# LF_ADC.net
KiCad netlist of a schematic drawn in Altium Designer
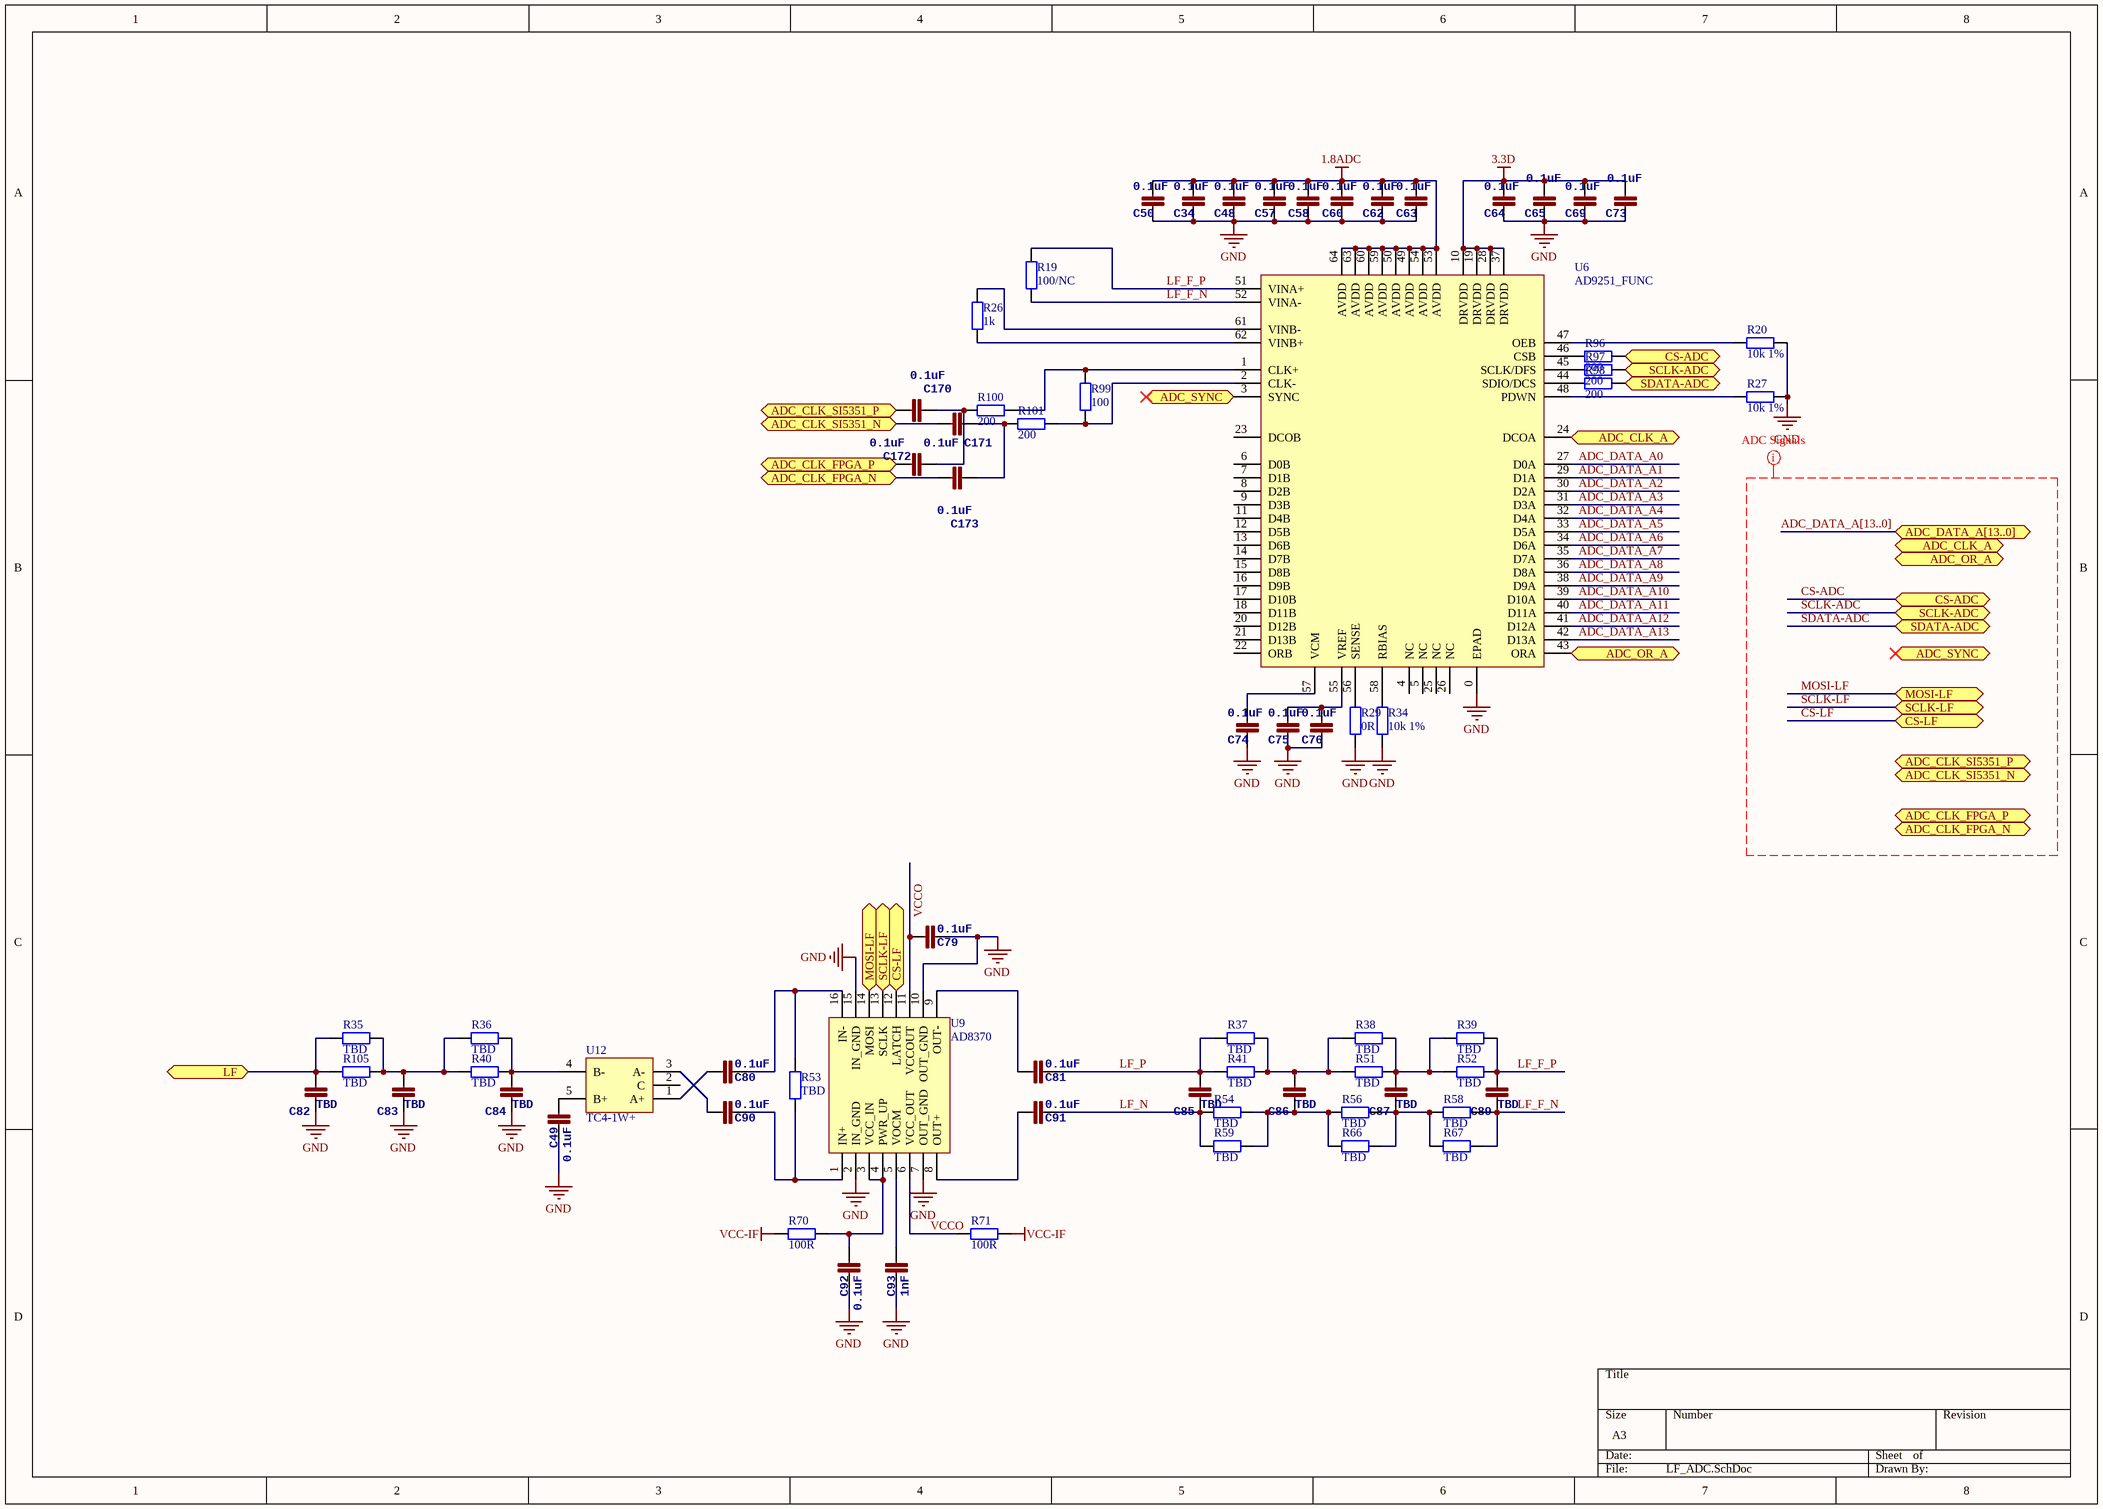
[diagram p0: LF_ADC.SchDoc]

(export (version "E")
  (design (tool "Eeschema 10.0.6"))
  (components
    (comp (ref "C34")
      (value "0.1uF")
      (footprint "0402")
      (description "<b>Capacitor</b>\nStandard 0603 ceramic capacitor, and 0.1\" leaded capacitor.")
      (fields (field (name "PARTNO") "CC0402ZRY5V7BB104"))
      (libsource (lib "*") (part "CAP0402-CAP"))
    )
    (comp (ref "C48")
      (value "0.1uF")
      (footprint "0402")
      (description "<b>Capacitor</b>\nStandard 0603 ceramic capacitor, and 0.1\" leaded capacitor.")
      (fields (field (name "PARTNO") "CC0402ZRY5V7BB104"))
      (libsource (lib "*") (part "CAP0402-CAP"))
    )
    (comp (ref "C49")
      (value "0.1uF")
      (footprint "0402")
      (description "<b>Capacitor</b>\nStandard 0603 ceramic capacitor, and 0.1\" leaded capacitor.")
      (fields (field (name "PARTNO") "CC0402ZRY5V7BB104"))
      (libsource (lib "*") (part "CAP0402-CAP"))
    )
    (comp (ref "C50")
      (value "0.1uF")
      (footprint "0402")
      (description "<b>Capacitor</b>\nStandard 0603 ceramic capacitor, and 0.1\" leaded capacitor.")
      (fields (field (name "PARTNO") "CC0402ZRY5V7BB104"))
      (libsource (lib "*") (part "CAP0402-CAP"))
    )
    (comp (ref "C57")
      (value "0.1uF")
      (footprint "0402")
      (description "<b>Capacitor</b>\nStandard 0603 ceramic capacitor, and 0.1\" leaded capacitor.")
      (fields (field (name "PARTNO") "CC0402ZRY5V7BB104"))
      (libsource (lib "*") (part "CAP0402-CAP"))
    )
    (comp (ref "C58")
      (value "0.1uF")
      (footprint "0402")
      (description "<b>Capacitor</b>\nStandard 0603 ceramic capacitor, and 0.1\" leaded capacitor.")
      (fields (field (name "PARTNO") "CC0402ZRY5V7BB104"))
      (libsource (lib "*") (part "CAP0402-CAP"))
    )
    (comp (ref "C60")
      (value "0.1uF")
      (footprint "0402")
      (description "<b>Capacitor</b>\nStandard 0603 ceramic capacitor, and 0.1\" leaded capacitor.")
      (fields (field (name "PARTNO") "CC0402ZRY5V7BB104"))
      (libsource (lib "*") (part "CAP0402-CAP"))
    )
    (comp (ref "C62")
      (value "0.1uF")
      (footprint "0402")
      (description "<b>Capacitor</b>\nStandard 0603 ceramic capacitor, and 0.1\" leaded capacitor.")
      (fields (field (name "PARTNO") "CC0402ZRY5V7BB104"))
      (libsource (lib "*") (part "CAP0402-CAP"))
    )
    (comp (ref "C63")
      (value "0.1uF")
      (footprint "0402")
      (description "<b>Capacitor</b>\nStandard 0603 ceramic capacitor, and 0.1\" leaded capacitor.")
      (fields (field (name "PARTNO") "CC0402ZRY5V7BB104"))
      (libsource (lib "*") (part "CAP0402-CAP"))
    )
    (comp (ref "C64")
      (value "0.1uF")
      (footprint "0402")
      (description "<b>Capacitor</b>\nStandard 0603 ceramic capacitor, and 0.1\" leaded capacitor.")
      (fields (field (name "PARTNO") "CC0402ZRY5V7BB104"))
      (libsource (lib "*") (part "CAP0402-CAP"))
    )
    (comp (ref "C65")
      (value "0.1uF")
      (footprint "0402")
      (description "<b>Capacitor</b>\nStandard 0603 ceramic capacitor, and 0.1\" leaded capacitor.")
      (fields (field (name "PARTNO") "CC0402ZRY5V7BB104"))
      (libsource (lib "*") (part "CAP0402-CAP"))
    )
    (comp (ref "C69")
      (value "0.1uF")
      (footprint "0402")
      (description "<b>Capacitor</b>\nStandard 0603 ceramic capacitor, and 0.1\" leaded capacitor.")
      (fields (field (name "PARTNO") "CC0402ZRY5V7BB104"))
      (libsource (lib "*") (part "CAP0402-CAP"))
    )
    (comp (ref "C73")
      (value "0.1uF")
      (footprint "0402")
      (description "<b>Capacitor</b>\nStandard 0603 ceramic capacitor, and 0.1\" leaded capacitor.")
      (fields (field (name "PARTNO") "CC0402ZRY5V7BB104"))
      (libsource (lib "*") (part "CAP0402-CAP"))
    )
    (comp (ref "C74")
      (value "0.1uF")
      (footprint "0402")
      (description "<b>Capacitor</b>\nStandard 0603 ceramic capacitor, and 0.1\" leaded capacitor.")
      (fields (field (name "PARTNO") "CC0402ZRY5V7BB104"))
      (libsource (lib "*") (part "CAP0402-CAP"))
    )
    (comp (ref "C75")
      (value "0.1uF")
      (footprint "0402")
      (description "<b>Capacitor</b>\nStandard 0603 ceramic capacitor, and 0.1\" leaded capacitor.")
      (fields (field (name "PARTNO") "CC0402ZRY5V7BB104"))
      (libsource (lib "*") (part "CAP0402-CAP"))
    )
    (comp (ref "C76")
      (value "0.1uF")
      (footprint "0402")
      (description "<b>Capacitor</b>\nStandard 0603 ceramic capacitor, and 0.1\" leaded capacitor.")
      (fields (field (name "PARTNO") "CC0402ZRY5V7BB104"))
      (libsource (lib "*") (part "CAP0402-CAP"))
    )
    (comp (ref "C79")
      (value "0.1uF")
      (footprint "0402")
      (description "<b>Capacitor</b>\nStandard 0603 ceramic capacitor, and 0.1\" leaded capacitor.")
      (fields (field (name "PARTNO") "CC0402ZRY5V7BB104"))
      (libsource (lib "") (part "CAP0402-CAP_1"))
    )
    (comp (ref "C80")
      (value "0.1uF")
      (footprint "0402")
      (description "<b>Capacitor</b>\nStandard 0603 ceramic capacitor, and 0.1\" leaded capacitor.")
      (fields (field (name "PARTNO") "CC0402ZRY5V7BB104"))
      (libsource (lib "") (part "CAP0402-CAP_1"))
    )
    (comp (ref "C81")
      (value "0.1uF")
      (footprint "0402")
      (description "<b>Capacitor</b>\nStandard 0603 ceramic capacitor, and 0.1\" leaded capacitor.")
      (fields (field (name "PARTNO") "CC0402ZRY5V7BB104"))
      (libsource (lib "") (part "CAP0402-CAP_1"))
    )
    (comp (ref "C82")
      (value "TBD")
      (footprint "0402")
      (description "<b>Capacitor</b>\nStandard 0603 ceramic capacitor, and 0.1\" leaded capacitor.")
      (fields (field (name "PARTNO") "CC0402ZRY5V7BB104"))
      (libsource (lib "") (part "CAP0402-CAP_2"))
    )
    (comp (ref "C83")
      (value "TBD")
      (footprint "0402")
      (description "<b>Capacitor</b>\nStandard 0603 ceramic capacitor, and 0.1\" leaded capacitor.")
      (fields (field (name "PARTNO") "CC0402ZRY5V7BB104"))
      (libsource (lib "") (part "CAP0402-CAP_2"))
    )
    (comp (ref "C84")
      (value "TBD")
      (footprint "0402")
      (description "<b>Capacitor</b>\nStandard 0603 ceramic capacitor, and 0.1\" leaded capacitor.")
      (fields (field (name "PARTNO") "CC0402ZRY5V7BB104"))
      (libsource (lib "") (part "CAP0402-CAP_2"))
    )
    (comp (ref "C85")
      (value "TBD")
      (footprint "0402")
      (description "<b>Capacitor</b>\nStandard 0603 ceramic capacitor, and 0.1\" leaded capacitor.")
      (fields (field (name "PARTNO") "CC0402ZRY5V7BB104"))
      (libsource (lib "") (part "CAP0402-CAP_2"))
    )
    (comp (ref "C86")
      (value "TBD")
      (footprint "0402")
      (description "<b>Capacitor</b>\nStandard 0603 ceramic capacitor, and 0.1\" leaded capacitor.")
      (fields (field (name "PARTNO") "CC0402ZRY5V7BB104"))
      (libsource (lib "") (part "CAP0402-CAP_2"))
    )
    (comp (ref "C87")
      (value "TBD")
      (footprint "0402")
      (description "<b>Capacitor</b>\nStandard 0603 ceramic capacitor, and 0.1\" leaded capacitor.")
      (fields (field (name "PARTNO") "CC0402ZRY5V7BB104"))
      (libsource (lib "") (part "CAP0402-CAP_2"))
    )
    (comp (ref "C89")
      (value "TBD")
      (footprint "0402")
      (description "<b>Capacitor</b>\nStandard 0603 ceramic capacitor, and 0.1\" leaded capacitor.")
      (fields (field (name "PARTNO") "CC0402ZRY5V7BB104"))
      (libsource (lib "") (part "CAP0402-CAP_2"))
    )
    (comp (ref "C90")
      (value "0.1uF")
      (footprint "0402")
      (description "<b>Capacitor</b>\nStandard 0603 ceramic capacitor, and 0.1\" leaded capacitor.")
      (fields (field (name "PARTNO") "CC0402ZRY5V7BB104"))
      (libsource (lib "") (part "CAP0402-CAP_1"))
    )
    (comp (ref "C91")
      (value "0.1uF")
      (footprint "0402")
      (description "<b>Capacitor</b>\nStandard 0603 ceramic capacitor, and 0.1\" leaded capacitor.")
      (fields (field (name "PARTNO") "CC0402ZRY5V7BB104"))
      (libsource (lib "") (part "CAP0402-CAP_1"))
    )
    (comp (ref "C92")
      (value "0.1uF")
      (footprint "0402")
      (description "<b>Capacitor</b>\nStandard 0603 ceramic capacitor, and 0.1\" leaded capacitor.")
      (fields (field (name "PARTNO") "CC0402ZRY5V7BB104"))
      (libsource (lib "*") (part "CAP0402-CAP"))
    )
    (comp (ref "C93")
      (value "1nF")
      (footprint "0402")
      (description "<b>Capacitor</b>\nStandard 0603 ceramic capacitor, and 0.1\" leaded capacitor.")
      (fields (field (name "PARTNO") "CC0402ZRY5V7BB104"))
      (libsource (lib "*") (part "CAP0402-CAP"))
    )
    (comp (ref "C170")
      (value "0.1uF")
      (footprint "0402")
      (description "<b>Capacitor</b>\nStandard 0603 ceramic capacitor, and 0.1\" leaded capacitor.")
      (fields (field (name "PARTNO") "CC0402ZRY5V7BB104"))
      (libsource (lib "") (part "CAP0402-CAP_1"))
    )
    (comp (ref "C171")
      (value "0.1uF")
      (footprint "0402")
      (description "<b>Capacitor</b>\nStandard 0603 ceramic capacitor, and 0.1\" leaded capacitor.")
      (fields (field (name "PARTNO") "CC0402ZRY5V7BB104"))
      (libsource (lib "") (part "CAP0402-CAP_1"))
    )
    (comp (ref "C172")
      (value "0.1uF")
      (footprint "0402")
      (description "<b>Capacitor</b>\nStandard 0603 ceramic capacitor, and 0.1\" leaded capacitor.")
      (fields (field (name "PARTNO") "CC0402ZRY5V7BB104"))
      (libsource (lib "") (part "CAP0402-CAP_1"))
    )
    (comp (ref "C173")
      (value "0.1uF")
      (footprint "0402")
      (description "<b>Capacitor</b>\nStandard 0603 ceramic capacitor, and 0.1\" leaded capacitor.")
      (fields (field (name "PARTNO") "CC0402ZRY5V7BB104"))
      (libsource (lib "") (part "CAP0402-CAP_1"))
    )
    (comp (ref "R19")
      (value "100/NC")
      (footprint "0402")
      (description "Resistor")
      (fields (field (name "PUBLISHER") "Altium Limited"))
      (libsource (lib "") (part "Res2_3"))
    )
    (comp (ref "R20")
      (value "10k 1%")
      (footprint "0402")
      (description "Resistor")
      (fields (field (name "PUBLISHER") "Altium Limited"))
      (libsource (lib "Miscellaneous Devices") (part "Res2"))
    )
    (comp (ref "R26")
      (value "1k")
      (footprint "0402")
      (description "Resistor")
      (fields (field (name "PUBLISHER") "Altium Limited"))
      (libsource (lib "") (part "Res2_3"))
    )
    (comp (ref "R27")
      (value "10k 1%")
      (footprint "0402")
      (description "Resistor")
      (fields (field (name "PUBLISHER") "Altium Limited"))
      (libsource (lib "Miscellaneous Devices") (part "Res2"))
    )
    (comp (ref "R29")
      (value "0R")
      (footprint "0402")
      (description "Resistor")
      (fields (field (name "PUBLISHER") "Altium Limited"))
      (libsource (lib "") (part "Res2_3"))
    )
    (comp (ref "R34")
      (value "10k 1%")
      (footprint "0402")
      (description "Resistor")
      (fields (field (name "PUBLISHER") "Altium Limited"))
      (libsource (lib "") (part "Res2_3"))
    )
    (comp (ref "R35")
      (value "TBD")
      (footprint "0402")
      (description "Resistor")
      (fields (field (name "PUBLISHER") "Altium Limited"))
      (libsource (lib "") (part "Res2_1"))
    )
    (comp (ref "R36")
      (value "TBD")
      (footprint "0402")
      (description "Resistor")
      (fields (field (name "PUBLISHER") "Altium Limited"))
      (libsource (lib "") (part "Res2_1"))
    )
    (comp (ref "R37")
      (value "TBD")
      (footprint "0402")
      (description "Resistor")
      (fields (field (name "PUBLISHER") "Altium Limited"))
      (libsource (lib "") (part "Res2_1"))
    )
    (comp (ref "R38")
      (value "TBD")
      (footprint "0402")
      (description "Resistor")
      (fields (field (name "PUBLISHER") "Altium Limited"))
      (libsource (lib "") (part "Res2_1"))
    )
    (comp (ref "R39")
      (value "TBD")
      (footprint "0402")
      (description "Resistor")
      (fields (field (name "PUBLISHER") "Altium Limited"))
      (libsource (lib "") (part "Res2_1"))
    )
    (comp (ref "R40")
      (value "TBD")
      (footprint "0402")
      (description "Resistor")
      (fields (field (name "PUBLISHER") "Altium Limited"))
      (libsource (lib "") (part "Res2_1"))
    )
    (comp (ref "R41")
      (value "TBD")
      (footprint "0402")
      (description "Resistor")
      (fields (field (name "PUBLISHER") "Altium Limited"))
      (libsource (lib "") (part "Res2_1"))
    )
    (comp (ref "R51")
      (value "TBD")
      (footprint "0402")
      (description "Resistor")
      (fields (field (name "PUBLISHER") "Altium Limited"))
      (libsource (lib "") (part "Res2_1"))
    )
    (comp (ref "R52")
      (value "TBD")
      (footprint "0402")
      (description "Resistor")
      (fields (field (name "PUBLISHER") "Altium Limited"))
      (libsource (lib "") (part "Res2_1"))
    )
    (comp (ref "R53")
      (value "TBD")
      (footprint "0402")
      (description "Resistor")
      (fields (field (name "PUBLISHER") "Altium Limited"))
      (libsource (lib "") (part "Res2_2"))
    )
    (comp (ref "R54")
      (value "TBD")
      (footprint "0402")
      (description "Resistor")
      (fields (field (name "PUBLISHER") "Altium Limited"))
      (libsource (lib "Miscellaneous Devices") (part "Res2"))
    )
    (comp (ref "R56")
      (value "TBD")
      (footprint "0402")
      (description "Resistor")
      (fields (field (name "PUBLISHER") "Altium Limited"))
      (libsource (lib "Miscellaneous Devices") (part "Res2"))
    )
    (comp (ref "R58")
      (value "TBD")
      (footprint "0402")
      (description "Resistor")
      (fields (field (name "PUBLISHER") "Altium Limited"))
      (libsource (lib "Miscellaneous Devices") (part "Res2"))
    )
    (comp (ref "R59")
      (value "TBD")
      (footprint "0402")
      (description "Resistor")
      (fields (field (name "PUBLISHER") "Altium Limited"))
      (libsource (lib "Miscellaneous Devices") (part "Res2"))
    )
    (comp (ref "R66")
      (value "TBD")
      (footprint "0402")
      (description "Resistor")
      (fields (field (name "PUBLISHER") "Altium Limited"))
      (libsource (lib "Miscellaneous Devices") (part "Res2"))
    )
    (comp (ref "R67")
      (value "TBD")
      (footprint "0402")
      (description "Resistor")
      (fields (field (name "PUBLISHER") "Altium Limited"))
      (libsource (lib "Miscellaneous Devices") (part "Res2"))
    )
    (comp (ref "R70")
      (value "100R")
      (footprint "0402")
      (description "Resistor")
      (fields (field (name "PUBLISHER") "Altium Limited"))
      (libsource (lib "") (part "Res2_1"))
    )
    (comp (ref "R71")
      (value "100R")
      (footprint "0402")
      (description "Resistor")
      (fields (field (name "PUBLISHER") "Altium Limited"))
      (libsource (lib "") (part "Res2_1"))
    )
    (comp (ref "R96")
      (value "200")
      (footprint "0402")
      (description "Resistor")
      (fields (field (name "PUBLISHER") "Altium Limited"))
      (libsource (lib "Miscellaneous Devices") (part "Res2"))
    )
    (comp (ref "R97")
      (value "200")
      (footprint "0402")
      (description "Resistor")
      (fields (field (name "PUBLISHER") "Altium Limited"))
      (libsource (lib "Miscellaneous Devices") (part "Res2"))
    )
    (comp (ref "R98")
      (value "200")
      (footprint "0402")
      (description "Resistor")
      (fields (field (name "PUBLISHER") "Altium Limited"))
      (libsource (lib "Miscellaneous Devices") (part "Res2"))
    )
    (comp (ref "R99")
      (value "100")
      (footprint "0402")
      (description "Resistor")
      (fields (field (name "PUBLISHER") "Altium Limited"))
      (libsource (lib "") (part "Res2_2"))
    )
    (comp (ref "R100")
      (value "200")
      (footprint "0402")
      (description "Resistor")
      (fields (field (name "PUBLISHER") "Altium Limited"))
      (libsource (lib "Miscellaneous Devices") (part "Res2"))
    )
    (comp (ref "R101")
      (value "200")
      (footprint "0402")
      (description "Resistor")
      (fields (field (name "PUBLISHER") "Altium Limited"))
      (libsource (lib "Miscellaneous Devices") (part "Res2"))
    )
    (comp (ref "R105")
      (value "TBD")
      (footprint "0402")
      (description "Resistor")
      (fields (field (name "PUBLISHER") "Altium Limited"))
      (libsource (lib "") (part "Res2_1"))
    )
    (comp (ref "U6")
      (value "AD9251_FUNC")
      (footprint "AD9251")
      (libsource (lib "F4SDR") (part "AD9251_FUNC"))
    )
    (comp (ref "U9")
      (value "AD8370")
      (footprint "TSSOP16_44MM_065P - duplicate")
      (libsource (lib "F4SDR") (part "AD8370"))
    )
    (comp (ref "U12")
      (value "TC4-1W+")
      (footprint "TCM-63AX+")
      (libsource (lib "F4SDR") (part "TCM1-1-13M+"))
    )
  )
  (nets
    (net (code "1") (name "/ADC_CLK_A") (class "Default")
      (node (ref "U6") (pin "24") (pinfunction "DCOA_24") (pintype "passive"))
    )
    (net (code "2") (name "/ADC_CLK_FPGA_N") (class "Default")
      (node (ref "C173") (pin "1") (pinfunction "1_1") (pintype "passive"))
    )
    (net (code "3") (name "/ADC_CLK_FPGA_P") (class "Default")
      (node (ref "C172") (pin "1") (pinfunction "1_1") (pintype "passive"))
    )
    (net (code "4") (name "/ADC_CLK_SI5351_N") (class "Default")
      (node (ref "C171") (pin "1") (pinfunction "1_1") (pintype "passive"))
    )
    (net (code "5") (name "/ADC_CLK_SI5351_P") (class "Default")
      (node (ref "C170") (pin "1") (pinfunction "1_1") (pintype "passive"))
    )
    (net (code "6") (name "/ADC_DATA_A0") (class "Default")
      (node (ref "U6") (pin "27") (pinfunction "D0A_27") (pintype "passive"))
    )
    (net (code "7") (name "/ADC_DATA_A1") (class "Default")
      (node (ref "U6") (pin "29") (pinfunction "D1A_29") (pintype "passive"))
    )
    (net (code "8") (name "/ADC_DATA_A2") (class "Default")
      (node (ref "U6") (pin "30") (pinfunction "D2A_30") (pintype "passive"))
    )
    (net (code "9") (name "/ADC_DATA_A3") (class "Default")
      (node (ref "U6") (pin "31") (pinfunction "D3A_31") (pintype "passive"))
    )
    (net (code "10") (name "/ADC_DATA_A4") (class "Default")
      (node (ref "U6") (pin "32") (pinfunction "D4A_32") (pintype "passive"))
    )
    (net (code "11") (name "/ADC_DATA_A5") (class "Default")
      (node (ref "U6") (pin "33") (pinfunction "D5A_33") (pintype "passive"))
    )
    (net (code "12") (name "/ADC_DATA_A6") (class "Default")
      (node (ref "U6") (pin "34") (pinfunction "D6A_34") (pintype "passive"))
    )
    (net (code "13") (name "/ADC_DATA_A7") (class "Default")
      (node (ref "U6") (pin "35") (pinfunction "D7A_35") (pintype "passive"))
    )
    (net (code "14") (name "/ADC_DATA_A8") (class "Default")
      (node (ref "U6") (pin "36") (pinfunction "D8A_36") (pintype "passive"))
    )
    (net (code "15") (name "/ADC_DATA_A9") (class "Default")
      (node (ref "U6") (pin "38") (pinfunction "D9A_38") (pintype "passive"))
    )
    (net (code "16") (name "/ADC_DATA_A10") (class "Default")
      (node (ref "U6") (pin "39") (pinfunction "D10A_39") (pintype "passive"))
    )
    (net (code "17") (name "/ADC_DATA_A11") (class "Default")
      (node (ref "U6") (pin "40") (pinfunction "D11A_40") (pintype "passive"))
    )
    (net (code "18") (name "/ADC_DATA_A12") (class "Default")
      (node (ref "U6") (pin "41") (pinfunction "D12A_41") (pintype "passive"))
    )
    (net (code "19") (name "/ADC_DATA_A13") (class "Default")
      (node (ref "U6") (pin "42") (pinfunction "D13A_42") (pintype "passive"))
    )
    (net (code "21") (name "/ADC_OR_A") (class "Default")
      (node (ref "U6") (pin "43") (pinfunction "ORA_43") (pintype "passive"))
    )
    (net (code "22") (name "/ADC_SYNC") (class "Default")
      (node (ref "U6") (pin "3") (pinfunction "SYNC_3") (pintype "passive"))
    )
    (net (code "23") (name "/CS-ADC") (class "Default")
      (node (ref "R96") (pin "1") (pinfunction "1_1") (pintype "passive"))
    )
    (net (code "24") (name "/CS-LF") (class "Default")
      (node (ref "U9") (pin "12") (pinfunction "LATCH_12") (pintype "passive"))
    )
    (net (code "25") (name "/LF") (class "Default")
      (node (ref "C82") (pin "2") (pinfunction "2_2") (pintype "passive"))
      (node (ref "R105") (pin "1") (pinfunction "1_1") (pintype "passive"))
      (node (ref "R35") (pin "1") (pinfunction "1_1") (pintype "passive"))
    )
    (net (code "26") (name "/LF_F_N") (class "Default")
      (node (ref "C89") (pin "1") (pinfunction "1_1") (pintype "passive"))
      (node (ref "R19") (pin "1") (pinfunction "1_1") (pintype "passive"))
      (node (ref "R58") (pin "1") (pinfunction "1_1") (pintype "passive"))
      (node (ref "R67") (pin "1") (pinfunction "1_1") (pintype "passive"))
      (node (ref "U6") (pin "52") (pinfunction "VINA-_52") (pintype "passive"))
    )
    (net (code "27") (name "/LF_F_P") (class "Default")
      (node (ref "C89") (pin "2") (pinfunction "2_2") (pintype "passive"))
      (node (ref "R19") (pin "2") (pinfunction "2_2") (pintype "passive"))
      (node (ref "R39") (pin "2") (pinfunction "2_2") (pintype "passive"))
      (node (ref "R52") (pin "2") (pinfunction "2_2") (pintype "passive"))
      (node (ref "U6") (pin "51") (pinfunction "VINA+_51") (pintype "passive"))
    )
    (net (code "28") (name "/LF_N") (class "Default")
      (node (ref "C85") (pin "1") (pinfunction "1_1") (pintype "passive"))
      (node (ref "C91") (pin "2") (pinfunction "2_2") (pintype "passive"))
      (node (ref "R54") (pin "2") (pinfunction "2_2") (pintype "passive"))
      (node (ref "R59") (pin "2") (pinfunction "2_2") (pintype "passive"))
    )
    (net (code "29") (name "/LF_P") (class "Default")
      (node (ref "C81") (pin "2") (pinfunction "2_2") (pintype "passive"))
      (node (ref "C85") (pin "2") (pinfunction "2_2") (pintype "passive"))
      (node (ref "R37") (pin "1") (pinfunction "1_1") (pintype "passive"))
      (node (ref "R41") (pin "1") (pinfunction "1_1") (pintype "passive"))
    )
    (net (code "30") (name "/MOSI-LF") (class "Default")
      (node (ref "U9") (pin "14") (pinfunction "MOSI_14") (pintype "passive"))
    )
    (net (code "31") (name "/SCLK-ADC") (class "Default")
      (node (ref "R97") (pin "1") (pinfunction "1_1") (pintype "passive"))
    )
    (net (code "32") (name "/SCLK-LF") (class "Default")
      (node (ref "U9") (pin "13") (pinfunction "SCLK_13") (pintype "passive"))
    )
    (net (code "33") (name "/SDATA-ADC") (class "Default")
      (node (ref "R98") (pin "1") (pinfunction "1_1") (pintype "passive"))
    )
    (net (code "34") (name "/VCCO") (class "Default")
      (node (ref "C79") (pin "1") (pinfunction "1_1") (pintype "passive"))
      (node (ref "R71") (pin "1") (pinfunction "1_1") (pintype "passive"))
      (node (ref "U9") (pin "11") (pinfunction "VCCOUT_11") (pintype "passive"))
      (node (ref "U9") (pin "6") (pinfunction "VCC_OUT_6") (pintype "passive"))
    )
    (net (code "35") (name "1.8ADC") (class "Default")
      (node (ref "C34") (pin "1") (pinfunction "1_1") (pintype "passive"))
      (node (ref "C48") (pin "1") (pinfunction "1_1") (pintype "passive"))
      (node (ref "C50") (pin "1") (pinfunction "1_1") (pintype "passive"))
      (node (ref "C57") (pin "1") (pinfunction "1_1") (pintype "passive"))
      (node (ref "C58") (pin "1") (pinfunction "1_1") (pintype "passive"))
      (node (ref "C60") (pin "1") (pinfunction "1_1") (pintype "passive"))
      (node (ref "C62") (pin "1") (pinfunction "1_1") (pintype "passive"))
      (node (ref "C63") (pin "1") (pinfunction "1_1") (pintype "passive"))
      (node (ref "U6") (pin "49") (pinfunction "AVDD_49") (pintype "passive"))
      (node (ref "U6") (pin "50") (pinfunction "AVDD_50") (pintype "passive"))
      (node (ref "U6") (pin "53") (pinfunction "AVDD_53") (pintype "passive"))
      (node (ref "U6") (pin "54") (pinfunction "AVDD_54") (pintype "passive"))
      (node (ref "U6") (pin "59") (pinfunction "AVDD_59") (pintype "passive"))
      (node (ref "U6") (pin "60") (pinfunction "AVDD_60") (pintype "passive"))
      (node (ref "U6") (pin "63") (pinfunction "AVDD_63") (pintype "passive"))
      (node (ref "U6") (pin "64") (pinfunction "AVDD_64") (pintype "passive"))
    )
    (net (code "36") (name "3.3D") (class "Default")
      (node (ref "C64") (pin "1") (pinfunction "1_1") (pintype "passive"))
      (node (ref "C65") (pin "1") (pinfunction "1_1") (pintype "passive"))
      (node (ref "C69") (pin "1") (pinfunction "1_1") (pintype "passive"))
      (node (ref "C73") (pin "1") (pinfunction "1_1") (pintype "passive"))
      (node (ref "U6") (pin "10") (pinfunction "DRVDD_10") (pintype "passive"))
      (node (ref "U6") (pin "19") (pinfunction "DRVDD_19") (pintype "passive"))
      (node (ref "U6") (pin "28") (pinfunction "DRVDD_28") (pintype "passive"))
      (node (ref "U6") (pin "37") (pinfunction "DRVDD_37") (pintype "passive"))
    )
    (net (code "37") (name "GND") (class "Default")
      (node (ref "C34") (pin "2") (pinfunction "2_2") (pintype "passive"))
      (node (ref "C48") (pin "2") (pinfunction "2_2") (pintype "passive"))
      (node (ref "C49") (pin "2") (pinfunction "2_2") (pintype "passive"))
      (node (ref "C50") (pin "2") (pinfunction "2_2") (pintype "passive"))
      (node (ref "C57") (pin "2") (pinfunction "2_2") (pintype "passive"))
      (node (ref "C58") (pin "2") (pinfunction "2_2") (pintype "passive"))
      (node (ref "C60") (pin "2") (pinfunction "2_2") (pintype "passive"))
      (node (ref "C62") (pin "2") (pinfunction "2_2") (pintype "passive"))
      (node (ref "C63") (pin "2") (pinfunction "2_2") (pintype "passive"))
      (node (ref "C64") (pin "2") (pinfunction "2_2") (pintype "passive"))
      (node (ref "C65") (pin "2") (pinfunction "2_2") (pintype "passive"))
      (node (ref "C69") (pin "2") (pinfunction "2_2") (pintype "passive"))
      (node (ref "C73") (pin "2") (pinfunction "2_2") (pintype "passive"))
      (node (ref "C74") (pin "2") (pinfunction "2_2") (pintype "passive"))
      (node (ref "C75") (pin "2") (pinfunction "2_2") (pintype "passive"))
      (node (ref "C76") (pin "2") (pinfunction "2_2") (pintype "passive"))
      (node (ref "C79") (pin "2") (pinfunction "2_2") (pintype "passive"))
      (node (ref "C82") (pin "1") (pinfunction "1_1") (pintype "passive"))
      (node (ref "C83") (pin "1") (pinfunction "1_1") (pintype "passive"))
      (node (ref "C84") (pin "1") (pinfunction "1_1") (pintype "passive"))
      (node (ref "C92") (pin "2") (pinfunction "2_2") (pintype "passive"))
      (node (ref "C93") (pin "2") (pinfunction "2_2") (pintype "passive"))
      (node (ref "R20") (pin "1") (pinfunction "1_1") (pintype "passive"))
      (node (ref "R27") (pin "1") (pinfunction "1_1") (pintype "passive"))
      (node (ref "R29") (pin "1") (pinfunction "1_1") (pintype "passive"))
      (node (ref "R34") (pin "1") (pinfunction "1_1") (pintype "passive"))
      (node (ref "U6") (pin "0") (pinfunction "EPAD_0") (pintype "passive"))
      (node (ref "U9") (pin "10") (pinfunction "OUT_GND_10") (pintype "passive"))
      (node (ref "U9") (pin "15") (pinfunction "IN_GND_15") (pintype "passive"))
      (node (ref "U9") (pin "2") (pinfunction "IN_GND_2") (pintype "passive"))
      (node (ref "U9") (pin "7") (pinfunction "OUT_GND_7") (pintype "passive"))
    )
    (net (code "38") (name "Net-(C83-Pad2)") (class "Default")
      (node (ref "C83") (pin "2") (pinfunction "2_2") (pintype "passive"))
      (node (ref "R105") (pin "2") (pinfunction "2_2") (pintype "passive"))
      (node (ref "R35") (pin "2") (pinfunction "2_2") (pintype "passive"))
      (node (ref "R36") (pin "1") (pinfunction "1_1") (pintype "passive"))
      (node (ref "R40") (pin "1") (pinfunction "1_1") (pintype "passive"))
    )
    (net (code "39") (name "Net-(C86-Pad1)") (class "Default")
      (node (ref "C86") (pin "1") (pinfunction "1_1") (pintype "passive"))
      (node (ref "R54") (pin "1") (pinfunction "1_1") (pintype "passive"))
      (node (ref "R56") (pin "2") (pinfunction "2_2") (pintype "passive"))
      (node (ref "R59") (pin "1") (pinfunction "1_1") (pintype "passive"))
      (node (ref "R66") (pin "2") (pinfunction "2_2") (pintype "passive"))
    )
    (net (code "40") (name "Net-(C86-Pad2)") (class "Default")
      (node (ref "C86") (pin "2") (pinfunction "2_2") (pintype "passive"))
      (node (ref "R37") (pin "2") (pinfunction "2_2") (pintype "passive"))
      (node (ref "R38") (pin "1") (pinfunction "1_1") (pintype "passive"))
      (node (ref "R41") (pin "2") (pinfunction "2_2") (pintype "passive"))
      (node (ref "R51") (pin "1") (pinfunction "1_1") (pintype "passive"))
    )
    (net (code "41") (name "Net-(C87-Pad1)") (class "Default")
      (node (ref "C87") (pin "1") (pinfunction "1_1") (pintype "passive"))
      (node (ref "R56") (pin "1") (pinfunction "1_1") (pintype "passive"))
      (node (ref "R58") (pin "2") (pinfunction "2_2") (pintype "passive"))
      (node (ref "R66") (pin "1") (pinfunction "1_1") (pintype "passive"))
      (node (ref "R67") (pin "2") (pinfunction "2_2") (pintype "passive"))
    )
    (net (code "42") (name "Net-(C87-Pad2)") (class "Default")
      (node (ref "C87") (pin "2") (pinfunction "2_2") (pintype "passive"))
      (node (ref "R38") (pin "2") (pinfunction "2_2") (pintype "passive"))
      (node (ref "R39") (pin "1") (pinfunction "1_1") (pintype "passive"))
      (node (ref "R51") (pin "2") (pinfunction "2_2") (pintype "passive"))
      (node (ref "R52") (pin "1") (pinfunction "1_1") (pintype "passive"))
    )
    (net (code "43") (name "Net-(C170-Pad2)") (class "Default")
      (node (ref "C170") (pin "2") (pinfunction "2_2") (pintype "passive"))
      (node (ref "C172") (pin "2") (pinfunction "2_2") (pintype "passive"))
      (node (ref "R100") (pin "2") (pinfunction "2_2") (pintype "passive"))
    )
    (net (code "44") (name "Net-(C171-Pad2)") (class "Default")
      (node (ref "C171") (pin "2") (pinfunction "2_2") (pintype "passive"))
      (node (ref "C173") (pin "2") (pinfunction "2_2") (pintype "passive"))
      (node (ref "R101") (pin "2") (pinfunction "2_2") (pintype "passive"))
    )
    (net (code "45") (name "Net-(U6-CLK+)") (class "Default")
      (node (ref "R100") (pin "1") (pinfunction "1_1") (pintype "passive"))
      (node (ref "R99") (pin "1") (pinfunction "1_1") (pintype "passive"))
      (node (ref "U6") (pin "1") (pinfunction "CLK+_1") (pintype "passive"))
    )
    (net (code "46") (name "Net-(U6-CLK-)") (class "Default")
      (node (ref "R101") (pin "1") (pinfunction "1_1") (pintype "passive"))
      (node (ref "R99") (pin "2") (pinfunction "2_2") (pintype "passive"))
      (node (ref "U6") (pin "2") (pinfunction "CLK-_2") (pintype "passive"))
    )
    (net (code "47") (name "Net-(U6-CSB)") (class "Default")
      (node (ref "R96") (pin "2") (pinfunction "2_2") (pintype "passive"))
      (node (ref "U6") (pin "46") (pinfunction "CSB_46") (pintype "passive"))
    )
    (net (code "48") (name "Net-(U6-OEB)") (class "Default")
      (node (ref "R20") (pin "2") (pinfunction "2_2") (pintype "passive"))
      (node (ref "U6") (pin "47") (pinfunction "OEB_47") (pintype "passive"))
    )
    (net (code "49") (name "Net-(U6-PDWN)") (class "Default")
      (node (ref "R27") (pin "2") (pinfunction "2_2") (pintype "passive"))
      (node (ref "U6") (pin "48") (pinfunction "PDWN_48") (pintype "passive"))
    )
    (net (code "50") (name "Net-(U6-RBIAS)") (class "Default")
      (node (ref "R34") (pin "2") (pinfunction "2_2") (pintype "passive"))
      (node (ref "U6") (pin "58") (pinfunction "RBIAS_58") (pintype "passive"))
    )
    (net (code "51") (name "Net-(U6-SCLK{slash}DFS)") (class "Default")
      (node (ref "R97") (pin "2") (pinfunction "2_2") (pintype "passive"))
      (node (ref "U6") (pin "45") (pinfunction "SCLK/DFS_45") (pintype "passive"))
    )
    (net (code "52") (name "Net-(U6-SDIO{slash}DCS)") (class "Default")
      (node (ref "R98") (pin "2") (pinfunction "2_2") (pintype "passive"))
      (node (ref "U6") (pin "44") (pinfunction "SDIO/DCS_44") (pintype "passive"))
    )
    (net (code "53") (name "Net-(U6-SENSE)") (class "Default")
      (node (ref "R29") (pin "2") (pinfunction "2_2") (pintype "passive"))
      (node (ref "U6") (pin "56") (pinfunction "SENSE_56") (pintype "passive"))
    )
    (net (code "54") (name "Net-(U6-VCM)") (class "Default")
      (node (ref "C74") (pin "1") (pinfunction "1_1") (pintype "passive"))
      (node (ref "U6") (pin "57") (pinfunction "VCM_57") (pintype "passive"))
    )
    (net (code "55") (name "Net-(U6-VINB+)") (class "Default")
      (node (ref "R26") (pin "1") (pinfunction "1_1") (pintype "passive"))
      (node (ref "U6") (pin "62") (pinfunction "VINB+_62") (pintype "passive"))
    )
    (net (code "56") (name "Net-(U6-VINB-)") (class "Default")
      (node (ref "R26") (pin "2") (pinfunction "2_2") (pintype "passive"))
      (node (ref "U6") (pin "61") (pinfunction "VINB-_61") (pintype "passive"))
    )
    (net (code "57") (name "Net-(U6-VREF)") (class "Default")
      (node (ref "C75") (pin "1") (pinfunction "1_1") (pintype "passive"))
      (node (ref "C76") (pin "1") (pinfunction "1_1") (pintype "passive"))
      (node (ref "U6") (pin "55") (pinfunction "VREF_55") (pintype "passive"))
    )
    (net (code "58") (name "Net-(U9-IN+)") (class "Default")
      (node (ref "C90") (pin "2") (pinfunction "2_2") (pintype "passive"))
      (node (ref "R53") (pin "2") (pinfunction "2_2") (pintype "passive"))
      (node (ref "U9") (pin "1") (pinfunction "IN+_1") (pintype "passive"))
    )
    (net (code "59") (name "Net-(U9-IN-)") (class "Default")
      (node (ref "C80") (pin "2") (pinfunction "2_2") (pintype "passive"))
      (node (ref "R53") (pin "1") (pinfunction "1_1") (pintype "passive"))
      (node (ref "U9") (pin "16") (pinfunction "IN-_16") (pintype "passive"))
    )
    (net (code "60") (name "Net-(U9-OUT+)") (class "Default")
      (node (ref "C91") (pin "1") (pinfunction "1_1") (pintype "passive"))
      (node (ref "U9") (pin "8") (pinfunction "OUT+_8") (pintype "passive"))
    )
    (net (code "61") (name "Net-(U9-OUT-)") (class "Default")
      (node (ref "C81") (pin "1") (pinfunction "1_1") (pintype "passive"))
      (node (ref "U9") (pin "9") (pinfunction "OUT-_9") (pintype "passive"))
    )
    (net (code "62") (name "Net-(U9-PWR_UP)") (class "Default")
      (node (ref "C92") (pin "1") (pinfunction "1_1") (pintype "passive"))
      (node (ref "R70") (pin "2") (pinfunction "2_2") (pintype "passive"))
      (node (ref "U9") (pin "3") (pinfunction "VCC_IN_3") (pintype "passive"))
      (node (ref "U9") (pin "4") (pinfunction "PWR_UP_4") (pintype "passive"))
    )
    (net (code "63") (name "Net-(U9-VOCM)") (class "Default")
      (node (ref "C93") (pin "1") (pinfunction "1_1") (pintype "passive"))
      (node (ref "U9") (pin "5") (pinfunction "VOCM_5") (pintype "passive"))
    )
    (net (code "64") (name "Net-(U12-A+)") (class "Default")
      (node (ref "C80") (pin "1") (pinfunction "1_1") (pintype "passive"))
      (node (ref "U12") (pin "1") (pinfunction "A+_1") (pintype "passive"))
    )
    (net (code "65") (name "Net-(U12-A-)") (class "Default")
      (node (ref "C90") (pin "1") (pinfunction "1_1") (pintype "passive"))
      (node (ref "U12") (pin "3") (pinfunction "A-_3") (pintype "passive"))
    )
    (net (code "66") (name "Net-(U12-B+)") (class "Default")
      (node (ref "C49") (pin "1") (pinfunction "1_1") (pintype "passive"))
      (node (ref "U12") (pin "5") (pinfunction "B+_5") (pintype "passive"))
    )
    (net (code "67") (name "Net-(U12-B-)") (class "Default")
      (node (ref "C84") (pin "2") (pinfunction "2_2") (pintype "passive"))
      (node (ref "R36") (pin "2") (pinfunction "2_2") (pintype "passive"))
      (node (ref "R40") (pin "2") (pinfunction "2_2") (pintype "passive"))
      (node (ref "U12") (pin "4") (pinfunction "B-_4") (pintype "passive"))
    )
    (net (code "68") (name "VCC-IF") (class "Default")
      (node (ref "R70") (pin "1") (pinfunction "1_1") (pintype "passive"))
      (node (ref "R71") (pin "2") (pinfunction "2_2") (pintype "passive"))
    )
    (net (code "69") (name "unconnected-(U6-D0B-Pad6)") (class "Default")
      (node (ref "U6") (pin "6") (pinfunction "D0B_6") (pintype "passive"))
    )
    (net (code "70") (name "unconnected-(U6-D1B-Pad7)") (class "Default")
      (node (ref "U6") (pin "7") (pinfunction "D1B_7") (pintype "passive"))
    )
    (net (code "71") (name "unconnected-(U6-D2B-Pad8)") (class "Default")
      (node (ref "U6") (pin "8") (pinfunction "D2B_8") (pintype "passive"))
    )
    (net (code "72") (name "unconnected-(U6-D3B-Pad9)") (class "Default")
      (node (ref "U6") (pin "9") (pinfunction "D3B_9") (pintype "passive"))
    )
    (net (code "73") (name "unconnected-(U6-D4B-Pad11)") (class "Default")
      (node (ref "U6") (pin "11") (pinfunction "D4B_11") (pintype "passive"))
    )
    (net (code "74") (name "unconnected-(U6-D5B-Pad12)") (class "Default")
      (node (ref "U6") (pin "12") (pinfunction "D5B_12") (pintype "passive"))
    )
    (net (code "75") (name "unconnected-(U6-D6B-Pad13)") (class "Default")
      (node (ref "U6") (pin "13") (pinfunction "D6B_13") (pintype "passive"))
    )
    (net (code "76") (name "unconnected-(U6-D7B-Pad14)") (class "Default")
      (node (ref "U6") (pin "14") (pinfunction "D7B_14") (pintype "passive"))
    )
    (net (code "77") (name "unconnected-(U6-D8B-Pad15)") (class "Default")
      (node (ref "U6") (pin "15") (pinfunction "D8B_15") (pintype "passive"))
    )
    (net (code "78") (name "unconnected-(U6-D9B-Pad16)") (class "Default")
      (node (ref "U6") (pin "16") (pinfunction "D9B_16") (pintype "passive"))
    )
    (net (code "79") (name "unconnected-(U6-D10B-Pad17)") (class "Default")
      (node (ref "U6") (pin "17") (pinfunction "D10B_17") (pintype "passive"))
    )
    (net (code "80") (name "unconnected-(U6-D11B-Pad18)") (class "Default")
      (node (ref "U6") (pin "18") (pinfunction "D11B_18") (pintype "passive"))
    )
    (net (code "81") (name "unconnected-(U6-D12B-Pad20)") (class "Default")
      (node (ref "U6") (pin "20") (pinfunction "D12B_20") (pintype "passive"))
    )
    (net (code "82") (name "unconnected-(U6-D13B-Pad21)") (class "Default")
      (node (ref "U6") (pin "21") (pinfunction "D13B_21") (pintype "passive"))
    )
    (net (code "83") (name "unconnected-(U6-DCOB-Pad23)") (class "Default")
      (node (ref "U6") (pin "23") (pinfunction "DCOB_23") (pintype "passive"))
    )
    (net (code "84") (name "unconnected-(U6-NC-Pad4)") (class "Default")
      (node (ref "U6") (pin "4") (pinfunction "NC_4") (pintype "passive"))
    )
    (net (code "85") (name "unconnected-(U6-NC-Pad5)") (class "Default")
      (node (ref "U6") (pin "5") (pinfunction "NC_5") (pintype "passive"))
    )
    (net (code "86") (name "unconnected-(U6-NC-Pad25)") (class "Default")
      (node (ref "U6") (pin "25") (pinfunction "NC_25") (pintype "passive"))
    )
    (net (code "87") (name "unconnected-(U6-NC-Pad26)") (class "Default")
      (node (ref "U6") (pin "26") (pinfunction "NC_26") (pintype "passive"))
    )
    (net (code "88") (name "unconnected-(U6-ORB-Pad22)") (class "Default")
      (node (ref "U6") (pin "22") (pinfunction "ORB_22") (pintype "passive"))
    )
    (net (code "89") (name "unconnected-(U12-C-Pad2)") (class "Default")
      (node (ref "U12") (pin "2") (pinfunction "C_2") (pintype "passive"))
    )
  )
)
